# SCH_flightcomputer-comminication_2025-01.net
KiCad netlist of a schematic drawn in EasyEDA
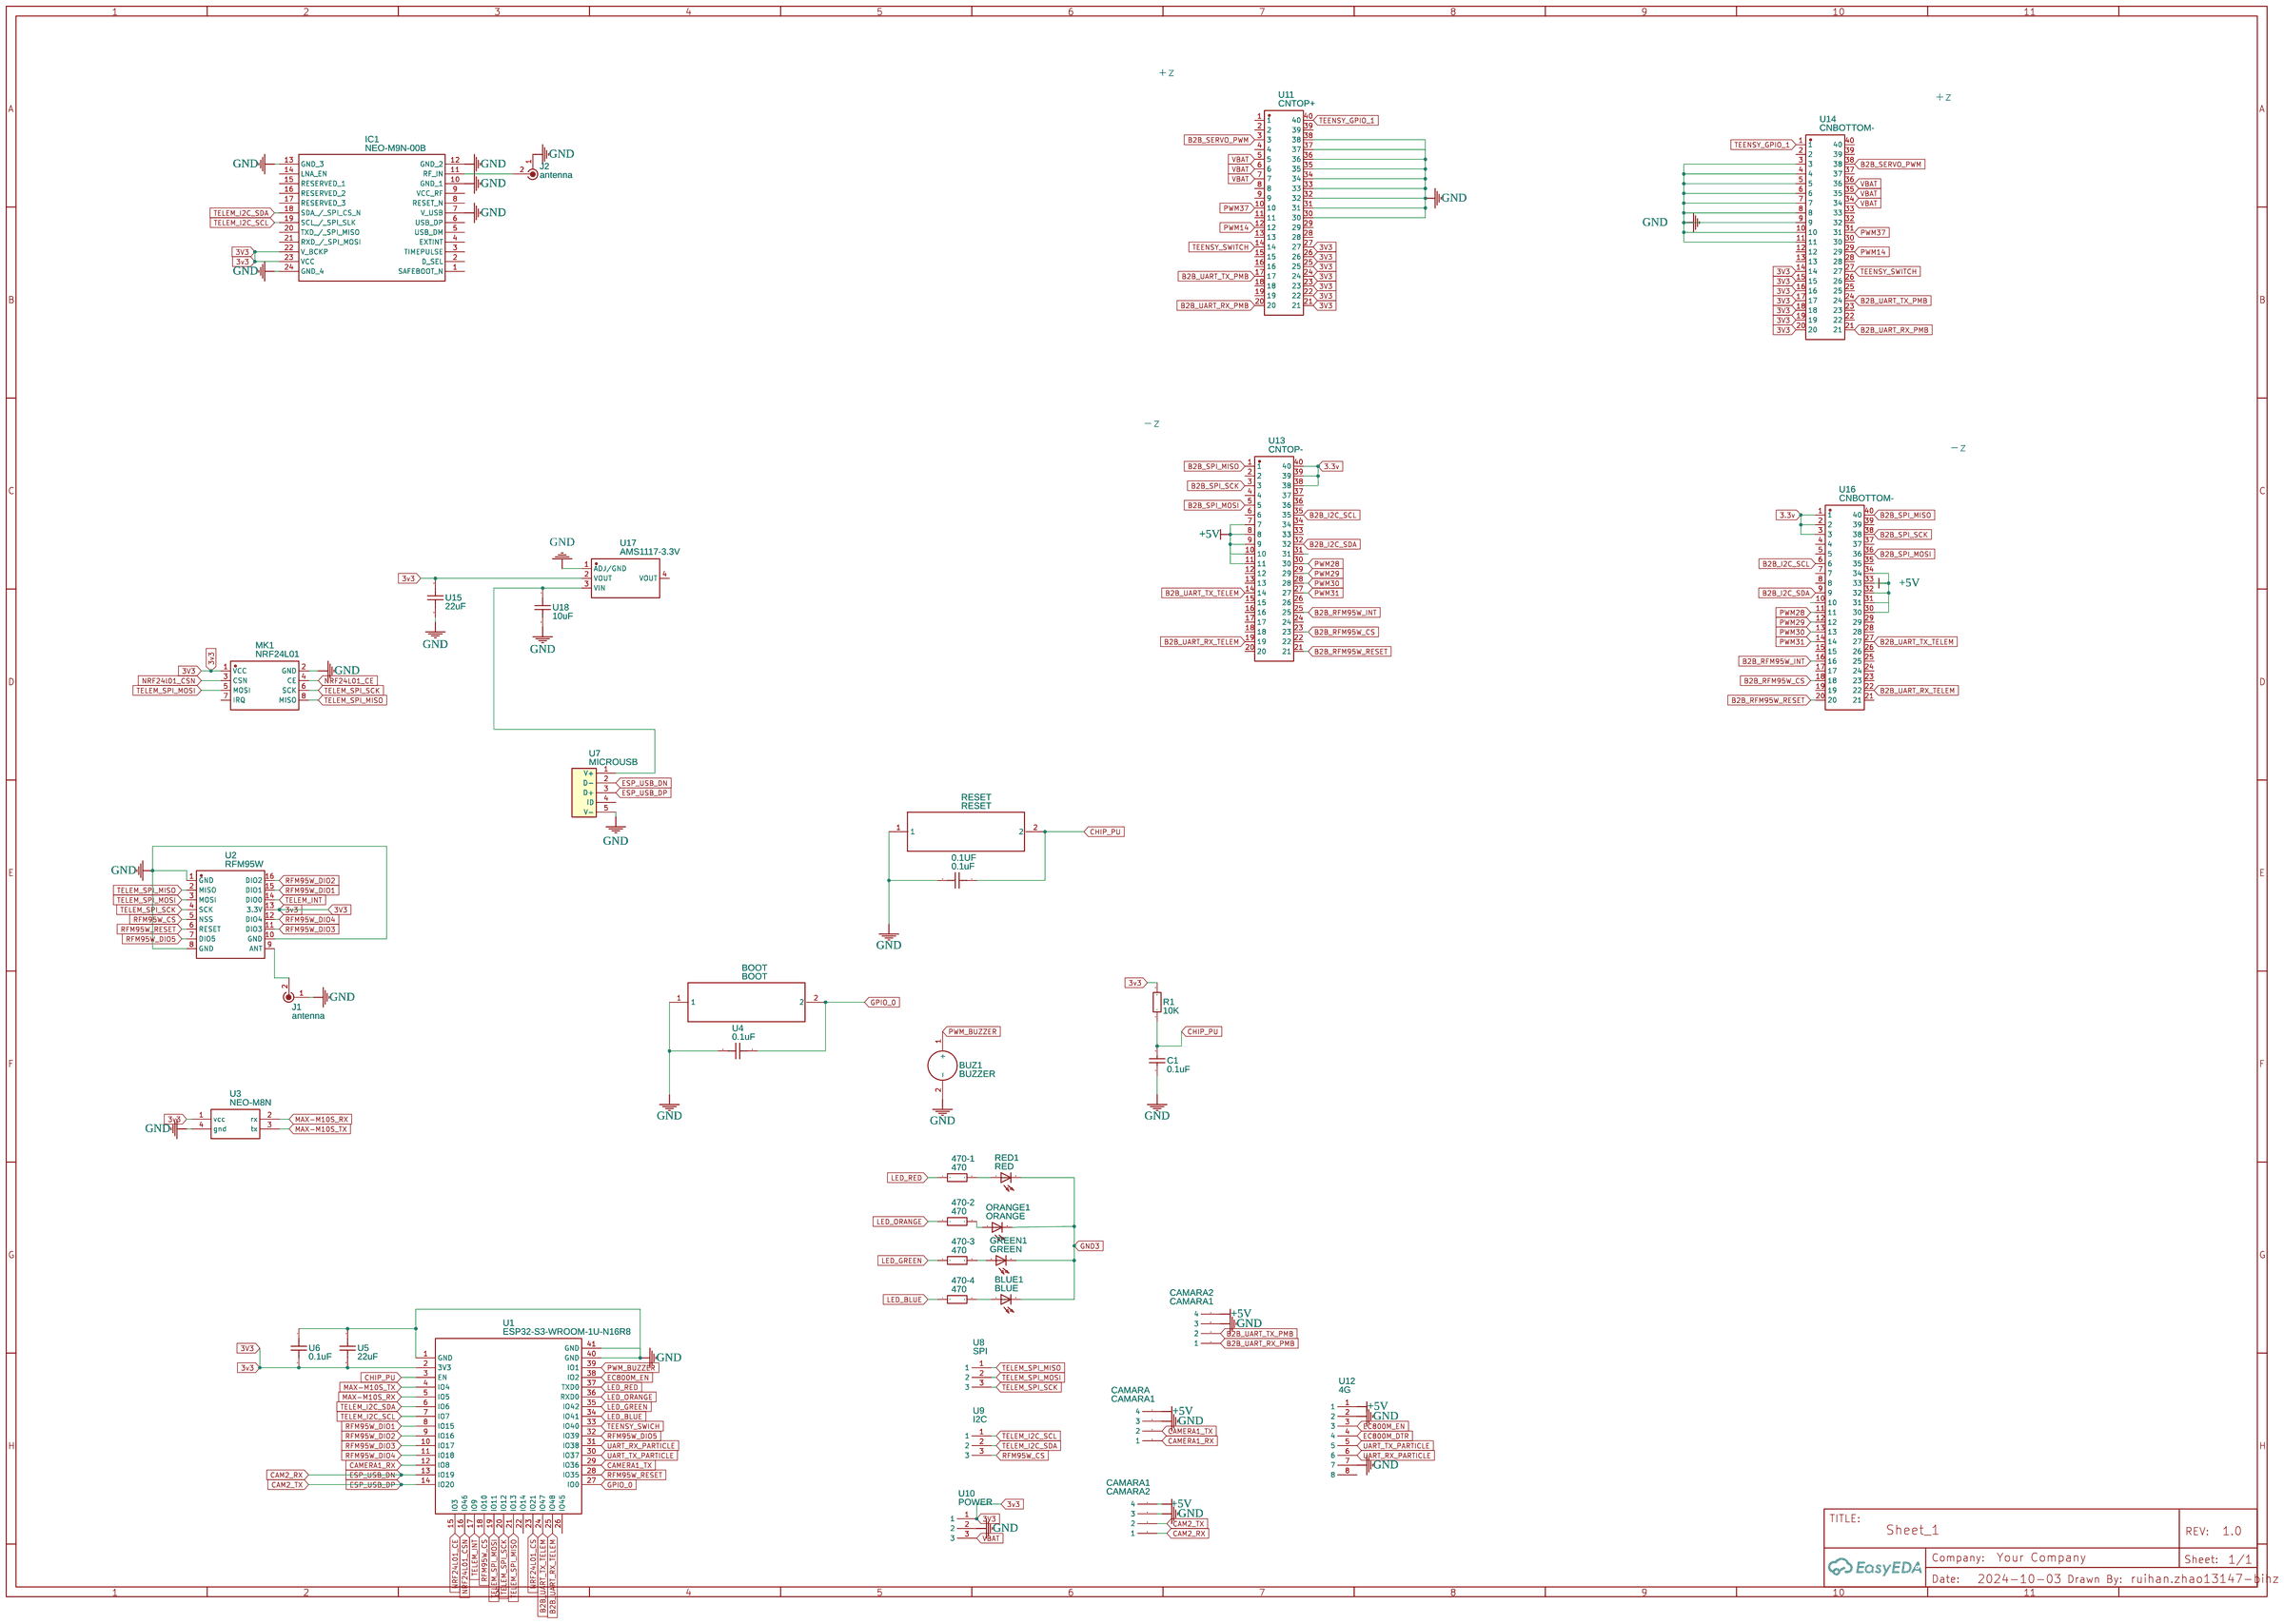
[diagram p0: schematic sheet]

(export (version "E")
  (design (tool "Eeschema 10.0.6"))
  (components
    (comp (ref "0.1UF")
      (value "0.1uF")
      (fields (field (name "Manufacturer Part") "CAP-C0805"))
      (libsource (lib "") (part "CAP-C0805_1"))
    )
    (comp (ref "470-1") (value "470") (libsource (lib "") (part "0805 Resistor")))
    (comp (ref "470-2") (value "470") (libsource (lib "") (part "0805 Resistor")))
    (comp (ref "470-3") (value "470") (libsource (lib "") (part "0805 Resistor")))
    (comp (ref "470-4") (value "470") (libsource (lib "") (part "0805 Resistor")))
    (comp (ref "BLUE1") (value "BLUE") (libsource (lib "") (part "LEDCHIP-LED0805")))
    (comp (ref "BOOT") (value "BOOT") (libsource (lib "") (part "FSMSM_1")))
    (comp (ref "BUZ1") (value "BUZZER") (libsource (lib "") (part "Buzzer_0905")))
    (comp (ref "C1")
      (value "0.1uF")
      (fields (field (name "Manufacturer") "SAMSUNG"))
      (libsource (lib "") (part "0805Cap"))
    )
    (comp (ref "CAMARA")
      (value "CAMARA1")
      (fields (field (name "Manufacturer Part") "4 Pin Header"))
      (libsource (lib "") (part "4 Pin Header"))
    )
    (comp (ref "CAMARA1")
      (value "CAMARA2")
      (fields (field (name "Manufacturer Part") "4 Pin Header"))
      (libsource (lib "") (part "4 Pin Header"))
    )
    (comp (ref "CAMARA2")
      (value "CAMARA1")
      (fields (field (name "Manufacturer Part") "4 Pin Header"))
      (libsource (lib "") (part "4 Pin Header"))
    )
    (comp (ref "GREEN1") (value "GREEN") (libsource (lib "") (part "LEDCHIP-LED0805_1")))
    (comp (ref "IC1") (value "NEO-M9N-00B") (libsource (lib "") (part "NEO-M9N-00B")))
    (comp (ref "J1")
      (value "antenna")
      (fields (field (name "Manufacturer") "Molex"))
      (libsource (lib "") (part "0734120114_1"))
    )
    (comp (ref "J2")
      (value "antenna")
      (fields (field (name "Manufacturer") "Molex"))
      (libsource (lib "") (part "0734120114"))
    )
    (comp (ref "MK1")
      (value "NRF24L01")
      (fields (field (name "Manufacturer Part") "NF-04") (field (name "Manufacturer") "Ai-Thinker(安信可)"))
      (libsource (lib "") (part "NRF24L01"))
    )
    (comp (ref "ORANGE1") (value "ORANGE") (libsource (lib "") (part "LEDCHIP-LED0805_3")))
    (comp (ref "R1")
      (value "10K")
      (fields (field (name "Manufacturer Part") "0805"))
      (libsource (lib "") (part "0805"))
    )
    (comp (ref "RED1") (value "RED") (libsource (lib "") (part "LEDCHIP-LED0805_2")))
    (comp (ref "RESET") (value "RESET") (libsource (lib "") (part "FSMSM")))
    (comp (ref "U1")
      (value "ESP32-S3-WROOM-1U-N16R8")
      (fields (field (name "Manufacturer") "ESPRESSIF(乐鑫)"))
      (libsource (lib "") (part "ESP32-S3-WROOM-1U-N16R8"))
    )
    (comp (ref "U2") (value "RFM95W") (libsource (lib "") (part "RFM95W")))
    (comp (ref "U3") (value "NEO-M8N") (libsource (lib "") (part "GY-GPS6MV2")))
    (comp (ref "U4")
      (value "0.1uF")
      (fields (field (name "Manufacturer Part") "CAP-C0805"))
      (libsource (lib "") (part "CAP-C0805_2"))
    )
    (comp (ref "U5")
      (value "22uF")
      (fields (field (name "Manufacturer Part") "CAP-C0805"))
      (libsource (lib "") (part "CAP-C0805"))
    )
    (comp (ref "U6")
      (value "0.1uF")
      (fields (field (name "Manufacturer Part") "CAP-C0805"))
      (libsource (lib "") (part "CAP-C0805"))
    )
    (comp (ref "U7") (value "MICROUSB") (libsource (lib "") (part "MICROUSB-FEMALE")))
    (comp (ref "U8") (value "SPI") (libsource (lib "") (part "3 pinheader")))
    (comp (ref "U9") (value "I2C") (libsource (lib "") (part "3 pinheader")))
    (comp (ref "U10") (value "POWER") (libsource (lib "") (part "3 pinheader")))
    (comp (ref "U11")
      (value "CNTOP+")
      (fields (field (name "Manufacturer Part") "SGDBM-08-40P"))
      (libsource (lib "") (part "SGDBM-08-40P"))
    )
    (comp (ref "U12") (value "4G") (libsource (lib "") (part "8pin header")))
    (comp (ref "U13")
      (value "CNTOP-")
      (fields (field (name "Manufacturer Part") "SGDBM-08-40P"))
      (libsource (lib "") (part "SGDBM-08-40P"))
    )
    (comp (ref "U14")
      (value "CNBOTTOM-")
      (fields (field (name "Manufacturer Part") "SGDBM-08-40P"))
      (libsource (lib "") (part "SGDBM-08-40P"))
    )
    (comp (ref "U15")
      (value "22uF")
      (fields (field (name "Manufacturer Part") "CAP-C0805"))
      (libsource (lib "") (part "CAP-C0805"))
    )
    (comp (ref "U16")
      (value "CNBOTTOM-")
      (fields (field (name "Manufacturer Part") "SGDBM-08-40P"))
      (libsource (lib "") (part "SGDBM-08-40P"))
    )
    (comp (ref "U17")
      (value "AMS1117-3.3V")
      (fields (field (name "Manufacturer") "WPMtek(维攀)"))
      (libsource (lib "") (part "AMS1117-3.3V"))
    )
    (comp (ref "U18")
      (value "10uF")
      (fields (field (name "Manufacturer Part") "CAP-C0805"))
      (libsource (lib "") (part "CAP-C0805"))
    )
  )
  (nets
    (net (code "1") (name "+5V") (class "Default")
      (node (ref "CAMARA") (pin "4") (pinfunction "4_4") (pintype "unspecified"))
      (node (ref "CAMARA1") (pin "4") (pinfunction "4_4") (pintype "unspecified"))
      (node (ref "CAMARA2") (pin "4") (pinfunction "4_4") (pintype "unspecified"))
      (node (ref "U12") (pin "1") (pinfunction "1_1") (pintype "unspecified"))
      (node (ref "U13") (pin "10") (pinfunction "10_10") (pintype "unspecified"))
      (node (ref "U13") (pin "11") (pinfunction "11_11") (pintype "unspecified"))
      (node (ref "U13") (pin "7") (pinfunction "7_7") (pintype "unspecified"))
      (node (ref "U13") (pin "8") (pinfunction "8_8") (pintype "unspecified"))
      (node (ref "U13") (pin "9") (pinfunction "9_9") (pintype "unspecified"))
      (node (ref "U16") (pin "30") (pinfunction "30_30") (pintype "unspecified"))
      (node (ref "U16") (pin "31") (pinfunction "31_31") (pintype "unspecified"))
      (node (ref "U16") (pin "32") (pinfunction "32_32") (pintype "unspecified"))
      (node (ref "U16") (pin "33") (pinfunction "33_33") (pintype "unspecified"))
      (node (ref "U16") (pin "34") (pinfunction "34_34") (pintype "unspecified"))
    )
    (net (code "2") (name "3.3v") (class "Default")
      (node (ref "U13") (pin "38") (pinfunction "38_38") (pintype "unspecified"))
      (node (ref "U13") (pin "39") (pinfunction "39_39") (pintype "unspecified"))
      (node (ref "U13") (pin "40") (pinfunction "40_40") (pintype "unspecified"))
      (node (ref "U16") (pin "1") (pinfunction "1_1") (pintype "unspecified"))
      (node (ref "U16") (pin "2") (pinfunction "2_2") (pintype "unspecified"))
      (node (ref "U16") (pin "3") (pinfunction "3_3") (pintype "unspecified"))
    )
    (net (code "3") (name "3V3") (class "Default")
      (node (ref "IC1") (pin "22") (pinfunction "V_BCKP_22") (pintype "bidirectional"))
      (node (ref "IC1") (pin "23") (pinfunction "VCC_23") (pintype "bidirectional"))
      (node (ref "MK1") (pin "1") (pinfunction "VCC_1") (pintype "unspecified"))
      (node (ref "R1") (pin "2") (pinfunction "2_2") (pintype "unspecified"))
      (node (ref "U1") (pin "2") (pinfunction "3V3_2") (pintype "passive"))
      (node (ref "U10") (pin "1") (pinfunction "1_1") (pintype "unspecified"))
      (node (ref "U11") (pin "21") (pinfunction "21_21") (pintype "unspecified"))
      (node (ref "U11") (pin "22") (pinfunction "22_22") (pintype "unspecified"))
      (node (ref "U11") (pin "23") (pinfunction "23_23") (pintype "unspecified"))
      (node (ref "U11") (pin "24") (pinfunction "24_24") (pintype "unspecified"))
      (node (ref "U11") (pin "25") (pinfunction "25_25") (pintype "unspecified"))
      (node (ref "U11") (pin "26") (pinfunction "26_26") (pintype "unspecified"))
      (node (ref "U11") (pin "27") (pinfunction "27_27") (pintype "unspecified"))
      (node (ref "U14") (pin "14") (pinfunction "14_14") (pintype "unspecified"))
      (node (ref "U14") (pin "15") (pinfunction "15_15") (pintype "unspecified"))
      (node (ref "U14") (pin "16") (pinfunction "16_16") (pintype "unspecified"))
      (node (ref "U14") (pin "17") (pinfunction "17_17") (pintype "unspecified"))
      (node (ref "U14") (pin "18") (pinfunction "18_18") (pintype "unspecified"))
      (node (ref "U14") (pin "19") (pinfunction "19_19") (pintype "unspecified"))
      (node (ref "U14") (pin "20") (pinfunction "20_20") (pintype "unspecified"))
      (node (ref "U15") (pin "1") (pinfunction "1_1") (pintype "unspecified"))
      (node (ref "U17") (pin "2") (pinfunction "VOUT_2") (pintype "unspecified"))
      (node (ref "U2") (pin "13") (pinfunction "3.3V_13") (pintype "unspecified"))
      (node (ref "U3") (pin "1") (pinfunction "vcc_1") (pintype "unspecified"))
      (node (ref "U5") (pin "2") (pinfunction "2_2") (pintype "unspecified"))
      (node (ref "U6") (pin "2") (pinfunction "2_2") (pintype "unspecified"))
    )
    (net (code "4") (name "B2B_I2C_SCL") (class "Default")
      (node (ref "U13") (pin "35") (pinfunction "35_35") (pintype "unspecified"))
      (node (ref "U16") (pin "6") (pinfunction "6_6") (pintype "unspecified"))
    )
    (net (code "5") (name "B2B_I2C_SDA") (class "Default")
      (node (ref "U13") (pin "32") (pinfunction "32_32") (pintype "unspecified"))
      (node (ref "U16") (pin "9") (pinfunction "9_9") (pintype "unspecified"))
    )
    (net (code "6") (name "B2B_RFM95W_CS") (class "Default")
      (node (ref "U13") (pin "23") (pinfunction "23_23") (pintype "unspecified"))
      (node (ref "U16") (pin "18") (pinfunction "18_18") (pintype "unspecified"))
    )
    (net (code "7") (name "B2B_RFM95W_INT") (class "Default")
      (node (ref "U13") (pin "25") (pinfunction "25_25") (pintype "unspecified"))
      (node (ref "U16") (pin "16") (pinfunction "16_16") (pintype "unspecified"))
    )
    (net (code "8") (name "B2B_RFM95W_RESET") (class "Default")
      (node (ref "U13") (pin "21") (pinfunction "21_21") (pintype "unspecified"))
      (node (ref "U16") (pin "20") (pinfunction "20_20") (pintype "unspecified"))
    )
    (net (code "9") (name "B2B_SERVO_PWM") (class "Default")
      (node (ref "U11") (pin "3") (pinfunction "3_3") (pintype "unspecified"))
      (node (ref "U14") (pin "38") (pinfunction "38_38") (pintype "unspecified"))
    )
    (net (code "10") (name "B2B_SPI_MISO") (class "Default")
      (node (ref "U13") (pin "1") (pinfunction "1_1") (pintype "unspecified"))
      (node (ref "U16") (pin "40") (pinfunction "40_40") (pintype "unspecified"))
    )
    (net (code "11") (name "B2B_SPI_MOSI") (class "Default")
      (node (ref "U13") (pin "5") (pinfunction "5_5") (pintype "unspecified"))
      (node (ref "U16") (pin "36") (pinfunction "36_36") (pintype "unspecified"))
    )
    (net (code "12") (name "B2B_SPI_SCK") (class "Default")
      (node (ref "U13") (pin "3") (pinfunction "3_3") (pintype "unspecified"))
      (node (ref "U16") (pin "38") (pinfunction "38_38") (pintype "unspecified"))
    )
    (net (code "13") (name "B2B_UART_RX_PMB") (class "Default")
      (node (ref "CAMARA2") (pin "1") (pinfunction "1_1") (pintype "unspecified"))
      (node (ref "U11") (pin "20") (pinfunction "20_20") (pintype "unspecified"))
      (node (ref "U14") (pin "21") (pinfunction "21_21") (pintype "unspecified"))
    )
    (net (code "14") (name "B2B_UART_RX_TELEM") (class "Default")
      (node (ref "U1") (pin "25") (pinfunction "IO48_25") (pintype "unspecified"))
      (node (ref "U13") (pin "19") (pinfunction "19_19") (pintype "unspecified"))
      (node (ref "U16") (pin "22") (pinfunction "22_22") (pintype "unspecified"))
    )
    (net (code "15") (name "B2B_UART_TX_PMB") (class "Default")
      (node (ref "CAMARA2") (pin "2") (pinfunction "2_2") (pintype "unspecified"))
      (node (ref "U11") (pin "17") (pinfunction "17_17") (pintype "unspecified"))
      (node (ref "U14") (pin "24") (pinfunction "24_24") (pintype "unspecified"))
    )
    (net (code "16") (name "B2B_UART_TX_TELEM") (class "Default")
      (node (ref "U1") (pin "24") (pinfunction "IO47_24") (pintype "unspecified"))
      (node (ref "U13") (pin "14") (pinfunction "14_14") (pintype "unspecified"))
      (node (ref "U16") (pin "27") (pinfunction "27_27") (pintype "unspecified"))
    )
    (net (code "17") (name "CAM2_RX") (class "Default")
      (node (ref "CAMARA1") (pin "1") (pinfunction "1_1") (pintype "unspecified"))
      (node (ref "U1") (pin "13") (pinfunction "IO19_13") (pintype "unspecified"))
      (node (ref "U7") (pin "2") (pinfunction "D-_2") (pintype "unspecified"))
    )
    (net (code "18") (name "CAM2_TX") (class "Default")
      (node (ref "CAMARA1") (pin "2") (pinfunction "2_2") (pintype "unspecified"))
      (node (ref "U1") (pin "14") (pinfunction "IO20_14") (pintype "unspecified"))
      (node (ref "U7") (pin "3") (pinfunction "D+_3") (pintype "unspecified"))
    )
    (net (code "19") (name "CAMERA1_RX") (class "Default")
      (node (ref "CAMARA") (pin "1") (pinfunction "1_1") (pintype "unspecified"))
      (node (ref "U1") (pin "12") (pinfunction "IO8_12") (pintype "unspecified"))
    )
    (net (code "20") (name "CAMERA1_TX") (class "Default")
      (node (ref "CAMARA") (pin "2") (pinfunction "2_2") (pintype "unspecified"))
      (node (ref "U1") (pin "29") (pinfunction "IO36_29") (pintype "unspecified"))
    )
    (net (code "21") (name "CHIP_PU") (class "Default")
      (node (ref "0.1UF") (pin "1") (pinfunction "1_1") (pintype "unspecified"))
      (node (ref "C1") (pin "2") (pinfunction "2_2") (pintype "input"))
      (node (ref "R1") (pin "1") (pinfunction "1_1") (pintype "unspecified"))
      (node (ref "RESET") (pin "2") (pinfunction "2_2") (pintype "bidirectional"))
      (node (ref "U1") (pin "3") (pinfunction "EN_3") (pintype "unspecified"))
    )
    (net (code "22") (name "EC800M_DTR") (class "Default")
      (node (ref "U12") (pin "4") (pinfunction "4_4") (pintype "unspecified"))
    )
    (net (code "23") (name "EC800M_EN") (class "Default")
      (node (ref "U1") (pin "38") (pinfunction "IO2_38") (pintype "unspecified"))
      (node (ref "U12") (pin "3") (pinfunction "3_3") (pintype "unspecified"))
    )
    (net (code "24") (name "GND") (class "Default")
      (node (ref "0.1UF") (pin "2") (pinfunction "2_2") (pintype "unspecified"))
      (node (ref "BOOT") (pin "1") (pinfunction "1_1") (pintype "bidirectional"))
      (node (ref "BUZ1") (pin "2") (pinfunction "-_2") (pintype "unspecified"))
      (node (ref "C1") (pin "1") (pinfunction "1_1") (pintype "input"))
      (node (ref "CAMARA") (pin "3") (pinfunction "3_3") (pintype "unspecified"))
      (node (ref "CAMARA1") (pin "3") (pinfunction "3_3") (pintype "unspecified"))
      (node (ref "CAMARA2") (pin "3") (pinfunction "3_3") (pintype "unspecified"))
      (node (ref "IC1") (pin "10") (pinfunction "GND_1_10") (pintype "bidirectional"))
      (node (ref "IC1") (pin "12") (pinfunction "GND_2_12") (pintype "bidirectional"))
      (node (ref "IC1") (pin "13") (pinfunction "GND_3_13") (pintype "bidirectional"))
      (node (ref "IC1") (pin "24") (pinfunction "GND_4_24") (pintype "bidirectional"))
      (node (ref "IC1") (pin "7") (pinfunction "V_USB_7") (pintype "bidirectional"))
      (node (ref "J1") (pin "1") (pintype "unspecified"))
      (node (ref "J2") (pin "1") (pintype "unspecified"))
      (node (ref "MK1") (pin "2") (pinfunction "GND_2") (pintype "unspecified"))
      (node (ref "RESET") (pin "1") (pinfunction "1_1") (pintype "bidirectional"))
      (node (ref "U1") (pin "1") (pinfunction "GND_1") (pintype "passive"))
      (node (ref "U1") (pin "40") (pinfunction "GND_40") (pintype "passive"))
      (node (ref "U1") (pin "41") (pinfunction "GND_41") (pintype "passive"))
      (node (ref "U10") (pin "2") (pinfunction "2_2") (pintype "unspecified"))
      (node (ref "U11") (pin "30") (pinfunction "30_30") (pintype "unspecified"))
      (node (ref "U11") (pin "31") (pinfunction "31_31") (pintype "unspecified"))
      (node (ref "U11") (pin "32") (pinfunction "32_32") (pintype "unspecified"))
      (node (ref "U11") (pin "33") (pinfunction "33_33") (pintype "unspecified"))
      (node (ref "U11") (pin "34") (pinfunction "34_34") (pintype "unspecified"))
      (node (ref "U11") (pin "35") (pinfunction "35_35") (pintype "unspecified"))
      (node (ref "U11") (pin "36") (pinfunction "36_36") (pintype "unspecified"))
      (node (ref "U11") (pin "37") (pinfunction "37_37") (pintype "unspecified"))
      (node (ref "U11") (pin "38") (pinfunction "38_38") (pintype "unspecified"))
      (node (ref "U12") (pin "2") (pinfunction "2_2") (pintype "unspecified"))
      (node (ref "U12") (pin "7") (pinfunction "7_7") (pintype "unspecified"))
      (node (ref "U14") (pin "10") (pinfunction "10_10") (pintype "unspecified"))
      (node (ref "U14") (pin "11") (pinfunction "11_11") (pintype "unspecified"))
      (node (ref "U14") (pin "3") (pinfunction "3_3") (pintype "unspecified"))
      (node (ref "U14") (pin "4") (pinfunction "4_4") (pintype "unspecified"))
      (node (ref "U14") (pin "5") (pinfunction "5_5") (pintype "unspecified"))
      (node (ref "U14") (pin "6") (pinfunction "6_6") (pintype "unspecified"))
      (node (ref "U14") (pin "7") (pinfunction "7_7") (pintype "unspecified"))
      (node (ref "U14") (pin "8") (pinfunction "8_8") (pintype "unspecified"))
      (node (ref "U14") (pin "9") (pinfunction "9_9") (pintype "unspecified"))
      (node (ref "U15") (pin "2") (pinfunction "2_2") (pintype "unspecified"))
      (node (ref "U17") (pin "1") (pinfunction "ADJ/GND_1") (pintype "unspecified"))
      (node (ref "U18") (pin "2") (pinfunction "2_2") (pintype "unspecified"))
      (node (ref "U2") (pin "1") (pinfunction "GND_1") (pintype "unspecified"))
      (node (ref "U2") (pin "10") (pinfunction "GND_10") (pintype "unspecified"))
      (node (ref "U2") (pin "8") (pinfunction "GND_8") (pintype "unspecified"))
      (node (ref "U3") (pin "4") (pinfunction "gnd_4") (pintype "unspecified"))
      (node (ref "U4") (pin "2") (pinfunction "2_2") (pintype "unspecified"))
      (node (ref "U5") (pin "1") (pinfunction "1_1") (pintype "unspecified"))
      (node (ref "U6") (pin "1") (pinfunction "1_1") (pintype "unspecified"))
      (node (ref "U7") (pin "5") (pinfunction "V-_5") (pintype "unspecified"))
    )
    (net (code "25") (name "GND3") (class "Default")
      (node (ref "BLUE1") (pin "C") (pinfunction "C_C") (pintype "bidirectional"))
      (node (ref "GREEN1") (pin "C") (pinfunction "C_C") (pintype "bidirectional"))
      (node (ref "ORANGE1") (pin "C") (pinfunction "C_C") (pintype "bidirectional"))
      (node (ref "RED1") (pin "C") (pinfunction "C_C") (pintype "bidirectional"))
    )
    (net (code "26") (name "GPIO_0") (class "Default")
      (node (ref "BOOT") (pin "2") (pinfunction "2_2") (pintype "bidirectional"))
      (node (ref "U1") (pin "27") (pinfunction "IO0_27") (pintype "unspecified"))
      (node (ref "U4") (pin "1") (pinfunction "1_1") (pintype "unspecified"))
    )
    (net (code "27") (name "LED_BLUE") (class "Default")
      (node (ref "470-4") (pin "1") (pinfunction "1_1") (pintype "unspecified"))
      (node (ref "U1") (pin "34") (pinfunction "IO41_34") (pintype "unspecified"))
    )
    (net (code "28") (name "LED_GREEN") (class "Default")
      (node (ref "470-3") (pin "1") (pinfunction "1_1") (pintype "unspecified"))
      (node (ref "U1") (pin "35") (pinfunction "IO42_35") (pintype "unspecified"))
    )
    (net (code "29") (name "LED_ORANGE") (class "Default")
      (node (ref "470-2") (pin "1") (pinfunction "1_1") (pintype "unspecified"))
      (node (ref "U1") (pin "36") (pinfunction "RXD0_36") (pintype "unspecified"))
    )
    (net (code "30") (name "LED_RED") (class "Default")
      (node (ref "470-1") (pin "1") (pinfunction "1_1") (pintype "unspecified"))
      (node (ref "U1") (pin "37") (pinfunction "TXD0_37") (pintype "unspecified"))
    )
    (net (code "31") (name "MAX-M10S_RX") (class "Default")
      (node (ref "U1") (pin "5") (pinfunction "IO5_5") (pintype "unspecified"))
      (node (ref "U3") (pin "2") (pinfunction "rx_2") (pintype "unspecified"))
    )
    (net (code "32") (name "MAX-M10S_TX") (class "Default")
      (node (ref "U1") (pin "4") (pinfunction "IO4_4") (pintype "unspecified"))
      (node (ref "U3") (pin "3") (pinfunction "tx_3") (pintype "unspecified"))
    )
    (net (code "33") (name "NRF24L01_CE") (class "Default")
      (node (ref "MK1") (pin "4") (pinfunction "CE_4") (pintype "unspecified"))
      (node (ref "U1") (pin "15") (pinfunction "IO3_15") (pintype "unspecified"))
    )
    (net (code "34") (name "NRF24L01_CS") (class "Default")
      (node (ref "U1") (pin "23") (pinfunction "IO21_23") (pintype "unspecified"))
    )
    (net (code "35") (name "NRF24L01_CSN") (class "Default")
      (node (ref "U1") (pin "16") (pinfunction "IO46_16") (pintype "unspecified"))
    )
    (net (code "36") (name "NRF24l01_CSN") (class "Default")
      (node (ref "MK1") (pin "3") (pinfunction "CSN_3") (pintype "unspecified"))
    )
    (net (code "37") (name "Net-(470-1-Pad2)") (class "Default")
      (node (ref "470-1") (pin "2") (pinfunction "2_2") (pintype "unspecified"))
      (node (ref "RED1") (pin "A") (pinfunction "A_A") (pintype "bidirectional"))
    )
    (net (code "38") (name "Net-(470-2-Pad2)") (class "Default")
      (node (ref "470-2") (pin "2") (pinfunction "2_2") (pintype "unspecified"))
      (node (ref "ORANGE1") (pin "A") (pinfunction "A_A") (pintype "bidirectional"))
    )
    (net (code "39") (name "Net-(470-3-Pad2)") (class "Default")
      (node (ref "470-3") (pin "2") (pinfunction "2_2") (pintype "unspecified"))
      (node (ref "GREEN1") (pin "A") (pinfunction "A_A") (pintype "bidirectional"))
    )
    (net (code "40") (name "Net-(470-4-Pad2)") (class "Default")
      (node (ref "470-4") (pin "2") (pinfunction "2_2") (pintype "unspecified"))
      (node (ref "BLUE1") (pin "A") (pinfunction "A_A") (pintype "bidirectional"))
    )
    (net (code "41") (name "Net-(IC1-RF_IN)") (class "Default")
      (node (ref "IC1") (pin "11") (pinfunction "RF_IN_11") (pintype "bidirectional"))
      (node (ref "J2") (pin "2") (pintype "unspecified"))
    )
    (net (code "42") (name "Net-(U2-ANT)") (class "Default")
      (node (ref "J1") (pin "2") (pintype "unspecified"))
      (node (ref "U2") (pin "9") (pinfunction "ANT_9") (pintype "unspecified"))
    )
    (net (code "43") (name "Net-(U17-VIN)") (class "Default")
      (node (ref "U17") (pin "3") (pinfunction "VIN_3") (pintype "unspecified"))
      (node (ref "U18") (pin "1") (pinfunction "1_1") (pintype "unspecified"))
      (node (ref "U7") (pin "1") (pinfunction "V+_1") (pintype "unspecified"))
    )
    (net (code "44") (name "PWM14") (class "Default")
      (node (ref "U11") (pin "12") (pinfunction "12_12") (pintype "unspecified"))
      (node (ref "U14") (pin "29") (pinfunction "29_29") (pintype "unspecified"))
    )
    (net (code "45") (name "PWM28") (class "Default")
      (node (ref "U13") (pin "30") (pinfunction "30_30") (pintype "unspecified"))
      (node (ref "U16") (pin "11") (pinfunction "11_11") (pintype "unspecified"))
    )
    (net (code "46") (name "PWM29") (class "Default")
      (node (ref "U13") (pin "29") (pinfunction "29_29") (pintype "unspecified"))
      (node (ref "U16") (pin "12") (pinfunction "12_12") (pintype "unspecified"))
    )
    (net (code "47") (name "PWM30") (class "Default")
      (node (ref "U13") (pin "28") (pinfunction "28_28") (pintype "unspecified"))
      (node (ref "U16") (pin "13") (pinfunction "13_13") (pintype "unspecified"))
    )
    (net (code "48") (name "PWM31") (class "Default")
      (node (ref "U13") (pin "27") (pinfunction "27_27") (pintype "unspecified"))
      (node (ref "U16") (pin "14") (pinfunction "14_14") (pintype "unspecified"))
    )
    (net (code "49") (name "PWM37") (class "Default")
      (node (ref "U11") (pin "10") (pinfunction "10_10") (pintype "unspecified"))
      (node (ref "U14") (pin "31") (pinfunction "31_31") (pintype "unspecified"))
    )
    (net (code "50") (name "PWM_BUZZER") (class "Default")
      (node (ref "BUZ1") (pin "1") (pinfunction "+_1") (pintype "unspecified"))
      (node (ref "U1") (pin "39") (pinfunction "IO1_39") (pintype "unspecified"))
    )
    (net (code "51") (name "RFM95W_CS") (class "Default")
      (node (ref "U1") (pin "18") (pinfunction "IO10_18") (pintype "unspecified"))
      (node (ref "U2") (pin "5") (pinfunction "NSS_5") (pintype "unspecified"))
      (node (ref "U9") (pin "3") (pinfunction "3_3") (pintype "unspecified"))
    )
    (net (code "52") (name "RFM95W_DIO1") (class "Default")
      (node (ref "U1") (pin "8") (pinfunction "IO15_8") (pintype "unspecified"))
      (node (ref "U2") (pin "15") (pinfunction "DIO1_15") (pintype "unspecified"))
    )
    (net (code "53") (name "RFM95W_DIO2") (class "Default")
      (node (ref "U1") (pin "9") (pinfunction "IO16_9") (pintype "unspecified"))
      (node (ref "U2") (pin "16") (pinfunction "DIO2_16") (pintype "unspecified"))
    )
    (net (code "54") (name "RFM95W_DIO3") (class "Default")
      (node (ref "U1") (pin "10") (pinfunction "IO17_10") (pintype "unspecified"))
      (node (ref "U2") (pin "11") (pinfunction "DIO3_11") (pintype "unspecified"))
    )
    (net (code "55") (name "RFM95W_DIO4") (class "Default")
      (node (ref "U1") (pin "11") (pinfunction "IO18_11") (pintype "unspecified"))
      (node (ref "U2") (pin "12") (pinfunction "DIO4_12") (pintype "unspecified"))
    )
    (net (code "56") (name "RFM95W_DIO5") (class "Default")
      (node (ref "U1") (pin "32") (pinfunction "IO39_32") (pintype "unspecified"))
      (node (ref "U2") (pin "7") (pinfunction "DIO5_7") (pintype "unspecified"))
    )
    (net (code "57") (name "RFM95W_RESET") (class "Default")
      (node (ref "U1") (pin "28") (pinfunction "IO35_28") (pintype "unspecified"))
      (node (ref "U2") (pin "6") (pinfunction "RESET_6") (pintype "unspecified"))
    )
    (net (code "58") (name "TEENSY_GPIO_1") (class "Default")
      (node (ref "U11") (pin "40") (pinfunction "40_40") (pintype "unspecified"))
      (node (ref "U14") (pin "1") (pinfunction "1_1") (pintype "unspecified"))
    )
    (net (code "59") (name "TEENSY_SWICH") (class "Default")
      (node (ref "U1") (pin "33") (pinfunction "IO40_33") (pintype "unspecified"))
    )
    (net (code "60") (name "TEENSY_SWITCH") (class "Default")
      (node (ref "U11") (pin "14") (pinfunction "14_14") (pintype "unspecified"))
      (node (ref "U14") (pin "27") (pinfunction "27_27") (pintype "unspecified"))
    )
    (net (code "61") (name "TELEM_I2C_SCL") (class "Default")
      (node (ref "IC1") (pin "19") (pinfunction "SCL_/_SPI_SLK_19") (pintype "bidirectional"))
      (node (ref "U1") (pin "7") (pinfunction "IO7_7") (pintype "unspecified"))
      (node (ref "U9") (pin "1") (pinfunction "1_1") (pintype "unspecified"))
    )
    (net (code "62") (name "TELEM_I2C_SDA") (class "Default")
      (node (ref "IC1") (pin "18") (pinfunction "SDA_/_SPI_CS_N_18") (pintype "bidirectional"))
      (node (ref "U1") (pin "6") (pinfunction "IO6_6") (pintype "unspecified"))
      (node (ref "U9") (pin "2") (pinfunction "2_2") (pintype "unspecified"))
    )
    (net (code "63") (name "TELEM_INT") (class "Default")
      (node (ref "U1") (pin "17") (pinfunction "IO9_17") (pintype "unspecified"))
      (node (ref "U2") (pin "14") (pinfunction "DIO0_14") (pintype "unspecified"))
    )
    (net (code "64") (name "TELEM_SPI_MISO") (class "Default")
      (node (ref "MK1") (pin "8") (pinfunction "MISO_8") (pintype "unspecified"))
      (node (ref "U1") (pin "21") (pinfunction "IO13_21") (pintype "unspecified"))
      (node (ref "U2") (pin "2") (pinfunction "MISO_2") (pintype "unspecified"))
      (node (ref "U8") (pin "1") (pinfunction "1_1") (pintype "unspecified"))
    )
    (net (code "65") (name "TELEM_SPI_MOSI") (class "Default")
      (node (ref "MK1") (pin "5") (pinfunction "MOSI_5") (pintype "unspecified"))
      (node (ref "U1") (pin "19") (pinfunction "IO11_19") (pintype "unspecified"))
      (node (ref "U2") (pin "3") (pinfunction "MOSI_3") (pintype "unspecified"))
      (node (ref "U8") (pin "2") (pinfunction "2_2") (pintype "unspecified"))
    )
    (net (code "66") (name "TELEM_SPI_SCK") (class "Default")
      (node (ref "MK1") (pin "6") (pinfunction "SCK_6") (pintype "unspecified"))
      (node (ref "U1") (pin "20") (pinfunction "IO12_20") (pintype "unspecified"))
      (node (ref "U2") (pin "4") (pinfunction "SCK_4") (pintype "unspecified"))
      (node (ref "U8") (pin "3") (pinfunction "3_3") (pintype "unspecified"))
    )
    (net (code "67") (name "UART_RX_PARTICLE") (class "Default")
      (node (ref "U1") (pin "31") (pinfunction "IO38_31") (pintype "unspecified"))
      (node (ref "U12") (pin "6") (pinfunction "6_6") (pintype "unspecified"))
    )
    (net (code "68") (name "UART_TX_PARTICLE") (class "Default")
      (node (ref "U1") (pin "30") (pinfunction "IO37_30") (pintype "unspecified"))
      (node (ref "U12") (pin "5") (pinfunction "5_5") (pintype "unspecified"))
    )
    (net (code "69") (name "VBAT") (class "Default")
      (node (ref "U10") (pin "3") (pinfunction "3_3") (pintype "unspecified"))
      (node (ref "U11") (pin "5") (pinfunction "5_5") (pintype "unspecified"))
      (node (ref "U11") (pin "6") (pinfunction "6_6") (pintype "unspecified"))
      (node (ref "U11") (pin "7") (pinfunction "7_7") (pintype "unspecified"))
      (node (ref "U14") (pin "34") (pinfunction "34_34") (pintype "unspecified"))
      (node (ref "U14") (pin "35") (pinfunction "35_35") (pintype "unspecified"))
      (node (ref "U14") (pin "36") (pinfunction "36_36") (pintype "unspecified"))
    )
    (net (code "70") (name "unconnected-(IC1-D_SEL-Pad2)") (class "Default")
      (node (ref "IC1") (pin "2") (pinfunction "D_SEL_2") (pintype "bidirectional"))
    )
    (net (code "71") (name "unconnected-(IC1-EXTINT-Pad4)") (class "Default")
      (node (ref "IC1") (pin "4") (pinfunction "EXTINT_4") (pintype "bidirectional"))
    )
    (net (code "72") (name "unconnected-(IC1-LNA_EN-Pad14)") (class "Default")
      (node (ref "IC1") (pin "14") (pinfunction "LNA_EN_14") (pintype "bidirectional"))
    )
    (net (code "73") (name "unconnected-(IC1-RESERVED_1-Pad15)") (class "Default")
      (node (ref "IC1") (pin "15") (pinfunction "RESERVED_1_15") (pintype "bidirectional"))
    )
    (net (code "74") (name "unconnected-(IC1-RESERVED_2-Pad16)") (class "Default")
      (node (ref "IC1") (pin "16") (pinfunction "RESERVED_2_16") (pintype "bidirectional"))
    )
    (net (code "75") (name "unconnected-(IC1-RESERVED_3-Pad17)") (class "Default")
      (node (ref "IC1") (pin "17") (pinfunction "RESERVED_3_17") (pintype "bidirectional"))
    )
    (net (code "76") (name "unconnected-(IC1-RESET_N-Pad8)") (class "Default")
      (node (ref "IC1") (pin "8") (pinfunction "RESET_N_8") (pintype "bidirectional"))
    )
    (net (code "77") (name "unconnected-(IC1-RXD_{slash}_SPI_MOSI-Pad21)") (class "Default")
      (node (ref "IC1") (pin "21") (pinfunction "RXD_/_SPI_MOSI_21") (pintype "bidirectional"))
    )
    (net (code "78") (name "unconnected-(IC1-SAFEBOOT_N-Pad1)") (class "Default")
      (node (ref "IC1") (pin "1") (pinfunction "SAFEBOOT_N_1") (pintype "bidirectional"))
    )
    (net (code "79") (name "unconnected-(IC1-TIMEPULSE-Pad3)") (class "Default")
      (node (ref "IC1") (pin "3") (pinfunction "TIMEPULSE_3") (pintype "bidirectional"))
    )
    (net (code "80") (name "unconnected-(IC1-TXD_{slash}_SPI_MISO-Pad20)") (class "Default")
      (node (ref "IC1") (pin "20") (pinfunction "TXD_/_SPI_MISO_20") (pintype "bidirectional"))
    )
    (net (code "81") (name "unconnected-(IC1-USB_DM-Pad5)") (class "Default")
      (node (ref "IC1") (pin "5") (pinfunction "USB_DM_5") (pintype "bidirectional"))
    )
    (net (code "82") (name "unconnected-(IC1-USB_DP-Pad6)") (class "Default")
      (node (ref "IC1") (pin "6") (pinfunction "USB_DP_6") (pintype "bidirectional"))
    )
    (net (code "83") (name "unconnected-(IC1-VCC_RF-Pad9)") (class "Default")
      (node (ref "IC1") (pin "9") (pinfunction "VCC_RF_9") (pintype "bidirectional"))
    )
    (net (code "84") (name "unconnected-(MK1-IRQ-Pad7)") (class "Default")
      (node (ref "MK1") (pin "7") (pinfunction "IRQ_7") (pintype "unspecified"))
    )
    (net (code "85") (name "unconnected-(U1-IO14-Pad22)") (class "Default")
      (node (ref "U1") (pin "22") (pinfunction "IO14_22") (pintype "unspecified"))
    )
    (net (code "86") (name "unconnected-(U1-IO45-Pad26)") (class "Default")
      (node (ref "U1") (pin "26") (pinfunction "IO45_26") (pintype "unspecified"))
    )
    (net (code "87") (name "unconnected-(U7-ID-Pad4)") (class "Default")
      (node (ref "U7") (pin "4") (pinfunction "ID_4") (pintype "unspecified"))
    )
    (net (code "88") (name "unconnected-(U11-Pad1)") (class "Default")
      (node (ref "U11") (pin "1") (pinfunction "1_1") (pintype "unspecified"))
    )
    (net (code "89") (name "unconnected-(U11-Pad2)") (class "Default")
      (node (ref "U11") (pin "2") (pinfunction "2_2") (pintype "unspecified"))
    )
    (net (code "90") (name "unconnected-(U11-Pad4)") (class "Default")
      (node (ref "U11") (pin "4") (pinfunction "4_4") (pintype "unspecified"))
    )
    (net (code "91") (name "unconnected-(U11-Pad8)") (class "Default")
      (node (ref "U11") (pin "8") (pinfunction "8_8") (pintype "unspecified"))
    )
    (net (code "92") (name "unconnected-(U11-Pad9)") (class "Default")
      (node (ref "U11") (pin "9") (pinfunction "9_9") (pintype "unspecified"))
    )
    (net (code "93") (name "unconnected-(U11-Pad11)") (class "Default")
      (node (ref "U11") (pin "11") (pinfunction "11_11") (pintype "unspecified"))
    )
    (net (code "94") (name "unconnected-(U11-Pad13)") (class "Default")
      (node (ref "U11") (pin "13") (pinfunction "13_13") (pintype "unspecified"))
    )
    (net (code "95") (name "unconnected-(U11-Pad15)") (class "Default")
      (node (ref "U11") (pin "15") (pinfunction "15_15") (pintype "unspecified"))
    )
    (net (code "96") (name "unconnected-(U11-Pad16)") (class "Default")
      (node (ref "U11") (pin "16") (pinfunction "16_16") (pintype "unspecified"))
    )
    (net (code "97") (name "unconnected-(U11-Pad18)") (class "Default")
      (node (ref "U11") (pin "18") (pinfunction "18_18") (pintype "unspecified"))
    )
    (net (code "98") (name "unconnected-(U11-Pad19)") (class "Default")
      (node (ref "U11") (pin "19") (pinfunction "19_19") (pintype "unspecified"))
    )
    (net (code "99") (name "unconnected-(U11-Pad28)") (class "Default")
      (node (ref "U11") (pin "28") (pinfunction "28_28") (pintype "unspecified"))
    )
    (net (code "100") (name "unconnected-(U11-Pad29)") (class "Default")
      (node (ref "U11") (pin "29") (pinfunction "29_29") (pintype "unspecified"))
    )
    (net (code "101") (name "unconnected-(U11-Pad39)") (class "Default")
      (node (ref "U11") (pin "39") (pinfunction "39_39") (pintype "unspecified"))
    )
    (net (code "102") (name "unconnected-(U12-Pad8)") (class "Default")
      (node (ref "U12") (pin "8") (pinfunction "8_8") (pintype "unspecified"))
    )
    (net (code "103") (name "unconnected-(U13-Pad2)") (class "Default")
      (node (ref "U13") (pin "2") (pinfunction "2_2") (pintype "unspecified"))
    )
    (net (code "104") (name "unconnected-(U13-Pad4)") (class "Default")
      (node (ref "U13") (pin "4") (pinfunction "4_4") (pintype "unspecified"))
    )
    (net (code "105") (name "unconnected-(U13-Pad6)") (class "Default")
      (node (ref "U13") (pin "6") (pinfunction "6_6") (pintype "unspecified"))
    )
    (net (code "106") (name "unconnected-(U13-Pad12)") (class "Default")
      (node (ref "U13") (pin "12") (pinfunction "12_12") (pintype "unspecified"))
    )
    (net (code "107") (name "unconnected-(U13-Pad13)") (class "Default")
      (node (ref "U13") (pin "13") (pinfunction "13_13") (pintype "unspecified"))
    )
    (net (code "108") (name "unconnected-(U13-Pad15)") (class "Default")
      (node (ref "U13") (pin "15") (pinfunction "15_15") (pintype "unspecified"))
    )
    (net (code "109") (name "unconnected-(U13-Pad16)") (class "Default")
      (node (ref "U13") (pin "16") (pinfunction "16_16") (pintype "unspecified"))
    )
    (net (code "110") (name "unconnected-(U13-Pad17)") (class "Default")
      (node (ref "U13") (pin "17") (pinfunction "17_17") (pintype "unspecified"))
    )
    (net (code "111") (name "unconnected-(U13-Pad18)") (class "Default")
      (node (ref "U13") (pin "18") (pinfunction "18_18") (pintype "unspecified"))
    )
    (net (code "112") (name "unconnected-(U13-Pad20)") (class "Default")
      (node (ref "U13") (pin "20") (pinfunction "20_20") (pintype "unspecified"))
    )
    (net (code "113") (name "unconnected-(U13-Pad22)") (class "Default")
      (node (ref "U13") (pin "22") (pinfunction "22_22") (pintype "unspecified"))
    )
    (net (code "114") (name "unconnected-(U13-Pad24)") (class "Default")
      (node (ref "U13") (pin "24") (pinfunction "24_24") (pintype "unspecified"))
    )
    (net (code "115") (name "unconnected-(U13-Pad26)") (class "Default")
      (node (ref "U13") (pin "26") (pinfunction "26_26") (pintype "unspecified"))
    )
    (net (code "116") (name "unconnected-(U13-Pad31)") (class "Default")
      (node (ref "U13") (pin "31") (pinfunction "31_31") (pintype "unspecified"))
    )
    (net (code "117") (name "unconnected-(U13-Pad33)") (class "Default")
      (node (ref "U13") (pin "33") (pinfunction "33_33") (pintype "unspecified"))
    )
    (net (code "118") (name "unconnected-(U13-Pad34)") (class "Default")
      (node (ref "U13") (pin "34") (pinfunction "34_34") (pintype "unspecified"))
    )
    (net (code "119") (name "unconnected-(U13-Pad36)") (class "Default")
      (node (ref "U13") (pin "36") (pinfunction "36_36") (pintype "unspecified"))
    )
    (net (code "120") (name "unconnected-(U13-Pad37)") (class "Default")
      (node (ref "U13") (pin "37") (pinfunction "37_37") (pintype "unspecified"))
    )
    (net (code "121") (name "unconnected-(U14-Pad2)") (class "Default")
      (node (ref "U14") (pin "2") (pinfunction "2_2") (pintype "unspecified"))
    )
    (net (code "122") (name "unconnected-(U14-Pad12)") (class "Default")
      (node (ref "U14") (pin "12") (pinfunction "12_12") (pintype "unspecified"))
    )
    (net (code "123") (name "unconnected-(U14-Pad13)") (class "Default")
      (node (ref "U14") (pin "13") (pinfunction "13_13") (pintype "unspecified"))
    )
    (net (code "124") (name "unconnected-(U14-Pad22)") (class "Default")
      (node (ref "U14") (pin "22") (pinfunction "22_22") (pintype "unspecified"))
    )
    (net (code "125") (name "unconnected-(U14-Pad23)") (class "Default")
      (node (ref "U14") (pin "23") (pinfunction "23_23") (pintype "unspecified"))
    )
    (net (code "126") (name "unconnected-(U14-Pad25)") (class "Default")
      (node (ref "U14") (pin "25") (pinfunction "25_25") (pintype "unspecified"))
    )
    (net (code "127") (name "unconnected-(U14-Pad26)") (class "Default")
      (node (ref "U14") (pin "26") (pinfunction "26_26") (pintype "unspecified"))
    )
    (net (code "128") (name "unconnected-(U14-Pad28)") (class "Default")
      (node (ref "U14") (pin "28") (pinfunction "28_28") (pintype "unspecified"))
    )
    (net (code "129") (name "unconnected-(U14-Pad30)") (class "Default")
      (node (ref "U14") (pin "30") (pinfunction "30_30") (pintype "unspecified"))
    )
    (net (code "130") (name "unconnected-(U14-Pad32)") (class "Default")
      (node (ref "U14") (pin "32") (pinfunction "32_32") (pintype "unspecified"))
    )
    (net (code "131") (name "unconnected-(U14-Pad33)") (class "Default")
      (node (ref "U14") (pin "33") (pinfunction "33_33") (pintype "unspecified"))
    )
    (net (code "132") (name "unconnected-(U14-Pad37)") (class "Default")
      (node (ref "U14") (pin "37") (pinfunction "37_37") (pintype "unspecified"))
    )
    (net (code "133") (name "unconnected-(U14-Pad39)") (class "Default")
      (node (ref "U14") (pin "39") (pinfunction "39_39") (pintype "unspecified"))
    )
    (net (code "134") (name "unconnected-(U14-Pad40)") (class "Default")
      (node (ref "U14") (pin "40") (pinfunction "40_40") (pintype "unspecified"))
    )
    (net (code "135") (name "unconnected-(U16-Pad4)") (class "Default")
      (node (ref "U16") (pin "4") (pinfunction "4_4") (pintype "unspecified"))
    )
    (net (code "136") (name "unconnected-(U16-Pad5)") (class "Default")
      (node (ref "U16") (pin "5") (pinfunction "5_5") (pintype "unspecified"))
    )
    (net (code "137") (name "unconnected-(U16-Pad7)") (class "Default")
      (node (ref "U16") (pin "7") (pinfunction "7_7") (pintype "unspecified"))
    )
    (net (code "138") (name "unconnected-(U16-Pad8)") (class "Default")
      (node (ref "U16") (pin "8") (pinfunction "8_8") (pintype "unspecified"))
    )
    (net (code "139") (name "unconnected-(U16-Pad10)") (class "Default")
      (node (ref "U16") (pin "10") (pinfunction "10_10") (pintype "unspecified"))
    )
    (net (code "140") (name "unconnected-(U16-Pad15)") (class "Default")
      (node (ref "U16") (pin "15") (pinfunction "15_15") (pintype "unspecified"))
    )
    (net (code "141") (name "unconnected-(U16-Pad17)") (class "Default")
      (node (ref "U16") (pin "17") (pinfunction "17_17") (pintype "unspecified"))
    )
    (net (code "142") (name "unconnected-(U16-Pad19)") (class "Default")
      (node (ref "U16") (pin "19") (pinfunction "19_19") (pintype "unspecified"))
    )
    (net (code "143") (name "unconnected-(U16-Pad21)") (class "Default")
      (node (ref "U16") (pin "21") (pinfunction "21_21") (pintype "unspecified"))
    )
    (net (code "144") (name "unconnected-(U16-Pad23)") (class "Default")
      (node (ref "U16") (pin "23") (pinfunction "23_23") (pintype "unspecified"))
    )
    (net (code "145") (name "unconnected-(U16-Pad24)") (class "Default")
      (node (ref "U16") (pin "24") (pinfunction "24_24") (pintype "unspecified"))
    )
    (net (code "146") (name "unconnected-(U16-Pad25)") (class "Default")
      (node (ref "U16") (pin "25") (pinfunction "25_25") (pintype "unspecified"))
    )
    (net (code "147") (name "unconnected-(U16-Pad26)") (class "Default")
      (node (ref "U16") (pin "26") (pinfunction "26_26") (pintype "unspecified"))
    )
    (net (code "148") (name "unconnected-(U16-Pad28)") (class "Default")
      (node (ref "U16") (pin "28") (pinfunction "28_28") (pintype "unspecified"))
    )
    (net (code "149") (name "unconnected-(U16-Pad29)") (class "Default")
      (node (ref "U16") (pin "29") (pinfunction "29_29") (pintype "unspecified"))
    )
    (net (code "150") (name "unconnected-(U16-Pad35)") (class "Default")
      (node (ref "U16") (pin "35") (pinfunction "35_35") (pintype "unspecified"))
    )
    (net (code "151") (name "unconnected-(U16-Pad37)") (class "Default")
      (node (ref "U16") (pin "37") (pinfunction "37_37") (pintype "unspecified"))
    )
    (net (code "152") (name "unconnected-(U16-Pad39)") (class "Default")
      (node (ref "U16") (pin "39") (pinfunction "39_39") (pintype "unspecified"))
    )
    (net (code "153") (name "unconnected-(U17-VOUT-Pad4)") (class "Default")
      (node (ref "U17") (pin "4") (pinfunction "VOUT_4") (pintype "unspecified"))
    )
  )
)
